# Megabit_FINAL_TOP.net
KiCad netlist of a schematic drawn in Altium Designer
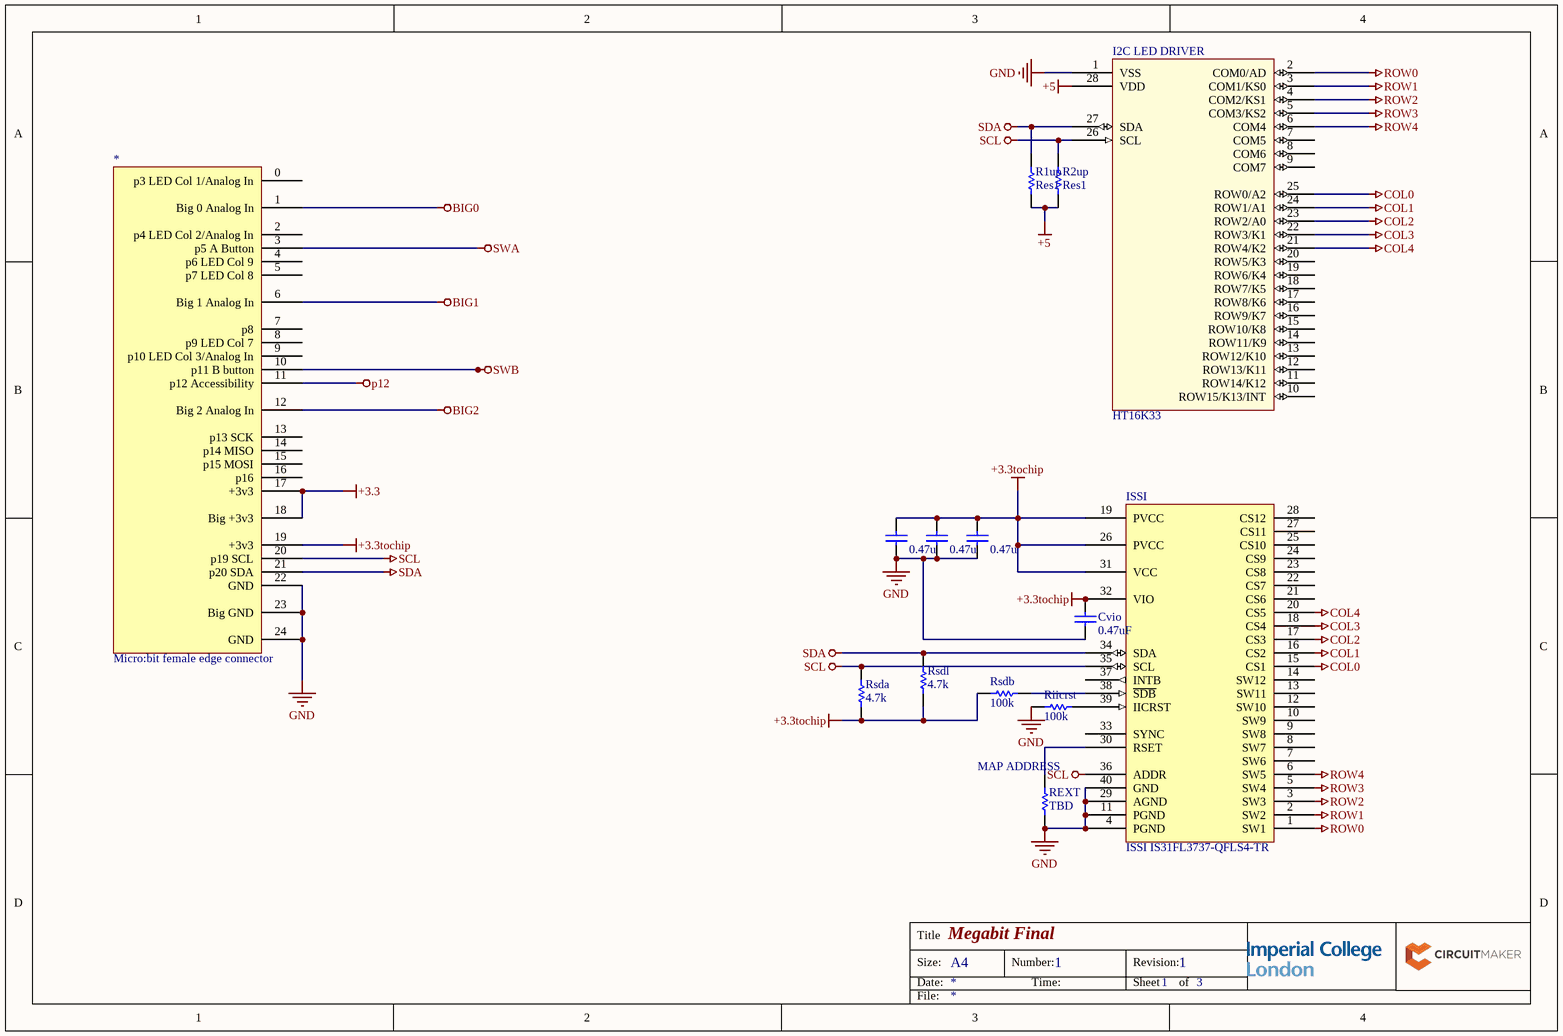
[diagram p0: Megabit FINAL TOP.SchDoc]

(export (version "E")
  (design (tool "Eeschema 10.0.6"))
  (components
    (comp (ref "*")
      (value "Micro:bit female edge connector")
      (footprint "PCBComponent_1 - duplicate")
      (description "http://www.dgyuliang.net/html/279.html")
      (libsource (lib "CommunityVault") (part "SYM-mom7rix79jkpy4z4w6go-1"))
    )
    (comp (ref "Cvcc1")
      (value "0.47u")
      (footprint "Vishay K104K15X7RF5TL2")
      (description "K Series 100nF 50 V ±10 % Tolerance X7R Radial Multilayer Ceramic Capacitor")
      (fields (field (name "MANUFACTURER PART NUMBER") "K104K15X7RF5TL2"))
      (libsource (lib "CommunityVault") (part "CMP-124240-16"))
    )
    (comp (ref "Cvcc2")
      (value "0.47u")
      (footprint "Vishay K104K15X7RF5TL2")
      (description "K Series 100nF 50 V ±10 % Tolerance X7R Radial Multilayer Ceramic Capacitor")
      (fields (field (name "MANUFACTURER PART NUMBER") "K104K15X7RF5TL2"))
      (libsource (lib "CommunityVault") (part "CMP-124240-16"))
    )
    (comp (ref "Cvcc3")
      (value "0.47u")
      (footprint "Vishay K104K15X7RF5TL2")
      (description "K Series 100nF 50 V ±10 % Tolerance X7R Radial Multilayer Ceramic Capacitor")
      (fields (field (name "MANUFACTURER PART NUMBER") "K104K15X7RF5TL2"))
      (libsource (lib "CommunityVault") (part "CMP-124240-16"))
    )
    (comp (ref "Cvio")
      (value "0.47uF")
      (footprint "Vishay K104K15X7RF5TL2")
      (description "K Series 100nF 50 V ±10 % Tolerance X7R Radial Multilayer Ceramic Capacitor")
      (fields (field (name "MANUFACTURER PART NUMBER") "K104K15X7RF5TL2"))
      (libsource (lib "CommunityVault") (part "CMP-124240-16"))
    )
    (comp (ref "I2C LED DRIVER")
      (value "HT16K33")
      (footprint "PCB-otwcc1b496jwxezlenqc-1")
      (description "3M(TM) Stikit(TM) Gold Disc Roll, 01427, 5 in, P100A, 125 discs per roll, 10 rolls per case")
      (libsource (lib "CommunityVault") (part "SYM-58709250411787b7-2"))
    )
    (comp (ref "ISSI")
      (value "ISSI IS31FL3737-QFLS4-TR")
      (footprint "QFN40")
      (description "LED Driver IC 24 Output Linear I²C Dimming 45mA 40-QFN (5x5)")
      (libsource (lib "CommunityVault") (part "SYM-21a7ec2d5ed8fe60-1"))
    )
    (comp (ref "R1up")
      (value "Res1")
      (footprint "PCB-3613466-1")
      (description "Resistor 0.25W")
      (libsource (lib "CommunityVault") (part "SYM-b15c796618a36e9b-1"))
    )
    (comp (ref "R2up")
      (value "Res1")
      (footprint "PCB-3613466-1")
      (description "Resistor 0.25W")
      (libsource (lib "CommunityVault") (part "SYM-b15c796618a36e9b-1"))
    )
    (comp (ref "REXT")
      (value "TBD")
      (footprint "PCB-3613466-1")
      (description "Resistor 0.25W")
      (libsource (lib "CommunityVault") (part "SYM-b15c796618a36e9b-1"))
    )
    (comp (ref "Riicrst")
      (value "100k")
      (footprint "PCB-3613466-1")
      (description "Resistor 0.25W")
      (libsource (lib "CommunityVault") (part "SYM-b15c796618a36e9b-1"))
    )
    (comp (ref "Rsda")
      (value "4.7k")
      (footprint "PCB-3613466-1")
      (description "Resistor 0.25W")
      (libsource (lib "CommunityVault") (part "SYM-b15c796618a36e9b-1"))
    )
    (comp (ref "Rsdb")
      (value "100k")
      (footprint "PCB-3613466-1")
      (description "Resistor 0.25W")
      (libsource (lib "CommunityVault") (part "SYM-b15c796618a36e9b-1"))
    )
    (comp (ref "Rsdl")
      (value "4.7k")
      (footprint "PCB-3613466-1")
      (description "Resistor 0.25W")
      (libsource (lib "CommunityVault") (part "SYM-b15c796618a36e9b-1"))
    )
  )
  (nets
    (net (code "1") (name "+3.3") (class "Default")
      (node (ref "*") (pin "17") (pinfunction "+3v3_17") (pintype "passive"))
      (node (ref "*") (pin "18") (pinfunction "Big_+3v3_18") (pintype "passive"))
    )
    (net (code "2") (name "+3.3tochip") (class "Default")
      (node (ref "*") (pin "19") (pinfunction "+3v3_19") (pintype "passive"))
      (node (ref "Cvcc1") (pin "2") (pinfunction "2_2") (pintype "passive"))
      (node (ref "Cvcc2") (pin "2") (pinfunction "2_2") (pintype "passive"))
      (node (ref "Cvcc3") (pin "2") (pinfunction "2_2") (pintype "passive"))
      (node (ref "Cvio") (pin "2") (pinfunction "2_2") (pintype "passive"))
      (node (ref "ISSI") (pin "19") (pinfunction "PVCC_19") (pintype "power_in"))
      (node (ref "ISSI") (pin "26") (pinfunction "PVCC_26") (pintype "passive"))
      (node (ref "ISSI") (pin "31") (pinfunction "VCC_31") (pintype "passive"))
      (node (ref "ISSI") (pin "32") (pinfunction "VIO_32") (pintype "power_in"))
      (node (ref "Rsda") (pin "2") (pinfunction "2_2") (pintype "passive"))
      (node (ref "Rsdb") (pin "2") (pinfunction "2_2") (pintype "passive"))
      (node (ref "Rsdl") (pin "2") (pinfunction "2_2") (pintype "passive"))
    )
    (net (code "3") (name "+5") (class "Default")
      (node (ref "I2C LED DRIVER") (pin "28") (pinfunction "VDD_28") (pintype "power_in"))
      (node (ref "R1up") (pin "1") (pinfunction "1_1") (pintype "passive"))
      (node (ref "R2up") (pin "1") (pinfunction "1_1") (pintype "passive"))
    )
    (net (code "4") (name "BIG0") (class "Default")
      (node (ref "*") (pin "1") (pinfunction "Big_0_Analog_In_1") (pintype "passive"))
    )
    (net (code "5") (name "BIG1") (class "Default")
      (node (ref "*") (pin "6") (pinfunction "Big_1_Analog_In_6") (pintype "passive"))
    )
    (net (code "6") (name "BIG2") (class "Default")
      (node (ref "*") (pin "12") (pinfunction "Big_2_Analog_In_12") (pintype "passive"))
    )
    (net (code "7") (name "COL0") (class "Default")
      (node (ref "I2C LED DRIVER") (pin "25") (pinfunction "ROW0/A2_25") (pintype "bidirectional"))
      (node (ref "ISSI") (pin "15") (pinfunction "CS1_15") (pintype "passive"))
    )
    (net (code "8") (name "COL1") (class "Default")
      (node (ref "I2C LED DRIVER") (pin "24") (pinfunction "ROW1/A1_24") (pintype "bidirectional"))
      (node (ref "ISSI") (pin "16") (pinfunction "CS2_16") (pintype "passive"))
    )
    (net (code "9") (name "COL2") (class "Default")
      (node (ref "I2C LED DRIVER") (pin "23") (pinfunction "ROW2/A0_23") (pintype "bidirectional"))
      (node (ref "ISSI") (pin "17") (pinfunction "CS3_17") (pintype "passive"))
    )
    (net (code "10") (name "COL3") (class "Default")
      (node (ref "I2C LED DRIVER") (pin "22") (pinfunction "ROW3/K1_22") (pintype "bidirectional"))
      (node (ref "ISSI") (pin "18") (pinfunction "CS4_18") (pintype "passive"))
    )
    (net (code "11") (name "COL4") (class "Default")
      (node (ref "I2C LED DRIVER") (pin "21") (pinfunction "ROW4/K2_21") (pintype "bidirectional"))
      (node (ref "ISSI") (pin "20") (pinfunction "CS5_20") (pintype "passive"))
    )
    (net (code "12") (name "GND") (class "Default")
      (node (ref "*") (pin "22") (pinfunction "GND_22") (pintype "passive"))
      (node (ref "*") (pin "23") (pinfunction "Big_GND_23") (pintype "passive"))
      (node (ref "*") (pin "24") (pinfunction "GND_24") (pintype "passive"))
      (node (ref "Cvcc1") (pin "1") (pinfunction "1_1") (pintype "passive"))
      (node (ref "Cvcc2") (pin "1") (pinfunction "1_1") (pintype "passive"))
      (node (ref "Cvcc3") (pin "1") (pinfunction "1_1") (pintype "passive"))
      (node (ref "Cvio") (pin "1") (pinfunction "1_1") (pintype "passive"))
      (node (ref "I2C LED DRIVER") (pin "1") (pinfunction "VSS_1") (pintype "power_in"))
      (node (ref "ISSI") (pin "11") (pinfunction "PGND_11") (pintype "power_in"))
      (node (ref "ISSI") (pin "29") (pinfunction "AGND_29") (pintype "power_in"))
      (node (ref "ISSI") (pin "4") (pinfunction "PGND_4") (pintype "power_in"))
      (node (ref "ISSI") (pin "40") (pinfunction "GND_40") (pintype "power_in"))
      (node (ref "REXT") (pin "1") (pinfunction "1_1") (pintype "passive"))
      (node (ref "Riicrst") (pin "2") (pinfunction "2_2") (pintype "passive"))
    )
    (net (code "13") (name "Net-(ISSI-IICRST)") (class "Default")
      (node (ref "ISSI") (pin "39") (pinfunction "IICRST_39") (pintype "input"))
      (node (ref "Riicrst") (pin "1") (pinfunction "1_1") (pintype "passive"))
    )
    (net (code "14") (name "Net-(ISSI-RSET)") (class "Default")
      (node (ref "ISSI") (pin "30") (pinfunction "RSET_30") (pintype "passive"))
      (node (ref "REXT") (pin "2") (pinfunction "2_2") (pintype "passive"))
    )
    (net (code "15") (name "Net-(ISSI-~{SDB})") (class "Default")
      (node (ref "ISSI") (pin "38") (pinfunction "~{SDB}_38") (pintype "input"))
      (node (ref "Rsdb") (pin "1") (pinfunction "1_1") (pintype "passive"))
    )
    (net (code "16") (name "ROW0") (class "Default")
      (node (ref "I2C LED DRIVER") (pin "2") (pinfunction "COM0/AD_2") (pintype "bidirectional"))
      (node (ref "ISSI") (pin "1") (pinfunction "SW1_1") (pintype "passive"))
    )
    (net (code "17") (name "ROW1") (class "Default")
      (node (ref "I2C LED DRIVER") (pin "3") (pinfunction "COM1/KS0_3") (pintype "bidirectional"))
      (node (ref "ISSI") (pin "2") (pinfunction "SW2_2") (pintype "passive"))
    )
    (net (code "18") (name "ROW2") (class "Default")
      (node (ref "I2C LED DRIVER") (pin "4") (pinfunction "COM2/KS1_4") (pintype "bidirectional"))
      (node (ref "ISSI") (pin "3") (pinfunction "SW3_3") (pintype "passive"))
    )
    (net (code "19") (name "ROW3") (class "Default")
      (node (ref "I2C LED DRIVER") (pin "5") (pinfunction "COM3/KS2_5") (pintype "bidirectional"))
      (node (ref "ISSI") (pin "5") (pinfunction "SW4_5") (pintype "passive"))
    )
    (net (code "20") (name "ROW4") (class "Default")
      (node (ref "I2C LED DRIVER") (pin "6") (pinfunction "COM4_6") (pintype "bidirectional"))
      (node (ref "ISSI") (pin "6") (pinfunction "SW5_6") (pintype "passive"))
    )
    (net (code "21") (name "SCL") (class "Default")
      (node (ref "*") (pin "20") (pinfunction "p19_SCL_20") (pintype "passive"))
      (node (ref "I2C LED DRIVER") (pin "26") (pinfunction "SCL_26") (pintype "input"))
      (node (ref "ISSI") (pin "35") (pinfunction "SCL_35") (pintype "bidirectional"))
      (node (ref "ISSI") (pin "36") (pinfunction "ADDR_36") (pintype "passive"))
      (node (ref "R2up") (pin "2") (pinfunction "2_2") (pintype "passive"))
      (node (ref "Rsda") (pin "1") (pinfunction "1_1") (pintype "passive"))
    )
    (net (code "22") (name "SDA") (class "Default")
      (node (ref "*") (pin "21") (pinfunction "p20_SDA_21") (pintype "passive"))
      (node (ref "I2C LED DRIVER") (pin "27") (pinfunction "SDA_27") (pintype "bidirectional"))
      (node (ref "ISSI") (pin "34") (pinfunction "SDA_34") (pintype "bidirectional"))
      (node (ref "R1up") (pin "2") (pinfunction "2_2") (pintype "passive"))
      (node (ref "Rsdl") (pin "1") (pinfunction "1_1") (pintype "passive"))
    )
    (net (code "23") (name "SWA") (class "Default")
      (node (ref "*") (pin "3") (pinfunction "p5_A_Button_3") (pintype "passive"))
    )
    (net (code "24") (name "SWB") (class "Default")
      (node (ref "*") (pin "10") (pinfunction "p11_B_button_10") (pintype "passive"))
    )
    (net (code "25") (name "p12") (class "Default")
      (node (ref "*") (pin "11") (pinfunction "p12_Accessibility_11") (pintype "passive"))
    )
    (net (code "26") (name "unconnected-(*-p3_LED_Col_1{slash}Analog_In-Pad0)") (class "Default")
      (node (ref "*") (pin "0") (pinfunction "p3_LED_Col_1/Analog_In_0") (pintype "passive"))
    )
    (net (code "27") (name "unconnected-(*-p4_LED_Col_2{slash}Analog_In-Pad2)") (class "Default")
      (node (ref "*") (pin "2") (pinfunction "p4_LED_Col_2/Analog_In_2") (pintype "passive"))
    )
    (net (code "28") (name "unconnected-(*-p6_LED_Col_9-Pad4)") (class "Default")
      (node (ref "*") (pin "4") (pinfunction "p6_LED_Col_9_4") (pintype "passive"))
    )
    (net (code "29") (name "unconnected-(*-p7_LED_Col_8-Pad5)") (class "Default")
      (node (ref "*") (pin "5") (pinfunction "p7_LED_Col_8_5") (pintype "passive"))
    )
    (net (code "30") (name "unconnected-(*-p8-Pad7)") (class "Default")
      (node (ref "*") (pin "7") (pinfunction "p8_7") (pintype "passive"))
    )
    (net (code "31") (name "unconnected-(*-p9_LED_Col_7-Pad8)") (class "Default")
      (node (ref "*") (pin "8") (pinfunction "p9_LED_Col_7_8") (pintype "passive"))
    )
    (net (code "32") (name "unconnected-(*-p10_LED_Col_3{slash}Analog_In-Pad9)") (class "Default")
      (node (ref "*") (pin "9") (pinfunction "p10_LED_Col_3/Analog_In_9") (pintype "passive"))
    )
    (net (code "33") (name "unconnected-(*-p13_SCK-Pad13)") (class "Default")
      (node (ref "*") (pin "13") (pinfunction "p13_SCK_13") (pintype "passive"))
    )
    (net (code "34") (name "unconnected-(*-p14_MISO-Pad14)") (class "Default")
      (node (ref "*") (pin "14") (pinfunction "p14_MISO_14") (pintype "passive"))
    )
    (net (code "35") (name "unconnected-(*-p15_MOSI-Pad15)") (class "Default")
      (node (ref "*") (pin "15") (pinfunction "p15_MOSI_15") (pintype "passive"))
    )
    (net (code "36") (name "unconnected-(*-p16-Pad16)") (class "Default")
      (node (ref "*") (pin "16") (pinfunction "p16_16") (pintype "passive"))
    )
    (net (code "37") (name "unconnected-(I2C LED DRIVER-COM5-Pad7)") (class "Default")
      (node (ref "I2C LED DRIVER") (pin "7") (pinfunction "COM5_7") (pintype "bidirectional"))
    )
    (net (code "38") (name "unconnected-(I2C LED DRIVER-COM6-Pad8)") (class "Default")
      (node (ref "I2C LED DRIVER") (pin "8") (pinfunction "COM6_8") (pintype "bidirectional"))
    )
    (net (code "39") (name "unconnected-(I2C LED DRIVER-COM7-Pad9)") (class "Default")
      (node (ref "I2C LED DRIVER") (pin "9") (pinfunction "COM7_9") (pintype "bidirectional"))
    )
    (net (code "40") (name "unconnected-(I2C LED DRIVER-ROW5{slash}K3-Pad20)") (class "Default")
      (node (ref "I2C LED DRIVER") (pin "20") (pinfunction "ROW5/K3_20") (pintype "bidirectional"))
    )
    (net (code "41") (name "unconnected-(I2C LED DRIVER-ROW6{slash}K4-Pad19)") (class "Default")
      (node (ref "I2C LED DRIVER") (pin "19") (pinfunction "ROW6/K4_19") (pintype "bidirectional"))
    )
    (net (code "42") (name "unconnected-(I2C LED DRIVER-ROW7{slash}K5-Pad18)") (class "Default")
      (node (ref "I2C LED DRIVER") (pin "18") (pinfunction "ROW7/K5_18") (pintype "bidirectional"))
    )
    (net (code "43") (name "unconnected-(I2C LED DRIVER-ROW8{slash}K6-Pad17)") (class "Default")
      (node (ref "I2C LED DRIVER") (pin "17") (pinfunction "ROW8/K6_17") (pintype "bidirectional"))
    )
    (net (code "44") (name "unconnected-(I2C LED DRIVER-ROW9{slash}K7-Pad16)") (class "Default")
      (node (ref "I2C LED DRIVER") (pin "16") (pinfunction "ROW9/K7_16") (pintype "bidirectional"))
    )
    (net (code "45") (name "unconnected-(I2C LED DRIVER-ROW10{slash}K8-Pad15)") (class "Default")
      (node (ref "I2C LED DRIVER") (pin "15") (pinfunction "ROW10/K8_15") (pintype "bidirectional"))
    )
    (net (code "46") (name "unconnected-(I2C LED DRIVER-ROW11{slash}K9-Pad14)") (class "Default")
      (node (ref "I2C LED DRIVER") (pin "14") (pinfunction "ROW11/K9_14") (pintype "bidirectional"))
    )
    (net (code "47") (name "unconnected-(I2C LED DRIVER-ROW12{slash}K10-Pad13)") (class "Default")
      (node (ref "I2C LED DRIVER") (pin "13") (pinfunction "ROW12/K10_13") (pintype "bidirectional"))
    )
    (net (code "48") (name "unconnected-(I2C LED DRIVER-ROW13{slash}K11-Pad12)") (class "Default")
      (node (ref "I2C LED DRIVER") (pin "12") (pinfunction "ROW13/K11_12") (pintype "bidirectional"))
    )
    (net (code "49") (name "unconnected-(I2C LED DRIVER-ROW14{slash}K12-Pad11)") (class "Default")
      (node (ref "I2C LED DRIVER") (pin "11") (pinfunction "ROW14/K12_11") (pintype "bidirectional"))
    )
    (net (code "50") (name "unconnected-(I2C LED DRIVER-ROW15{slash}K13{slash}INT-Pad10)") (class "Default")
      (node (ref "I2C LED DRIVER") (pin "10") (pinfunction "ROW15/K13/INT_10") (pintype "bidirectional"))
    )
    (net (code "51") (name "unconnected-(ISSI-CS6-Pad21)") (class "Default")
      (node (ref "ISSI") (pin "21") (pinfunction "CS6_21") (pintype "passive"))
    )
    (net (code "52") (name "unconnected-(ISSI-CS7-Pad22)") (class "Default")
      (node (ref "ISSI") (pin "22") (pinfunction "CS7_22") (pintype "passive"))
    )
    (net (code "53") (name "unconnected-(ISSI-CS8-Pad23)") (class "Default")
      (node (ref "ISSI") (pin "23") (pinfunction "CS8_23") (pintype "passive"))
    )
    (net (code "54") (name "unconnected-(ISSI-CS9-Pad24)") (class "Default")
      (node (ref "ISSI") (pin "24") (pinfunction "CS9_24") (pintype "passive"))
    )
    (net (code "55") (name "unconnected-(ISSI-CS10-Pad25)") (class "Default")
      (node (ref "ISSI") (pin "25") (pinfunction "CS10_25") (pintype "passive"))
    )
    (net (code "56") (name "unconnected-(ISSI-CS11-Pad27)") (class "Default")
      (node (ref "ISSI") (pin "27") (pinfunction "CS11_27") (pintype "passive"))
    )
    (net (code "57") (name "unconnected-(ISSI-CS12-Pad28)") (class "Default")
      (node (ref "ISSI") (pin "28") (pinfunction "CS12_28") (pintype "passive"))
    )
    (net (code "58") (name "unconnected-(ISSI-INTB-Pad37)") (class "Default")
      (node (ref "ISSI") (pin "37") (pinfunction "INTB_37") (pintype "output"))
    )
    (net (code "59") (name "unconnected-(ISSI-SW6-Pad7)") (class "Default")
      (node (ref "ISSI") (pin "7") (pinfunction "SW6_7") (pintype "passive"))
    )
    (net (code "60") (name "unconnected-(ISSI-SW7-Pad8)") (class "Default")
      (node (ref "ISSI") (pin "8") (pinfunction "SW7_8") (pintype "passive"))
    )
    (net (code "61") (name "unconnected-(ISSI-SW8-Pad9)") (class "Default")
      (node (ref "ISSI") (pin "9") (pinfunction "SW8_9") (pintype "passive"))
    )
    (net (code "62") (name "unconnected-(ISSI-SW9-Pad10)") (class "Default")
      (node (ref "ISSI") (pin "10") (pinfunction "SW9_10") (pintype "passive"))
    )
    (net (code "63") (name "unconnected-(ISSI-SW10-Pad12)") (class "Default")
      (node (ref "ISSI") (pin "12") (pinfunction "SW10_12") (pintype "passive"))
    )
    (net (code "64") (name "unconnected-(ISSI-SW11-Pad13)") (class "Default")
      (node (ref "ISSI") (pin "13") (pinfunction "SW11_13") (pintype "passive"))
    )
    (net (code "65") (name "unconnected-(ISSI-SW12-Pad14)") (class "Default")
      (node (ref "ISSI") (pin "14") (pinfunction "SW12_14") (pintype "passive"))
    )
    (net (code "66") (name "unconnected-(ISSI-SYNC-Pad33)") (class "Default")
      (node (ref "ISSI") (pin "33") (pinfunction "SYNC_33") (pintype "passive"))
    )
  )
)
